# Connectors_1.net
KiCad netlist of a schematic drawn in Altium Designer
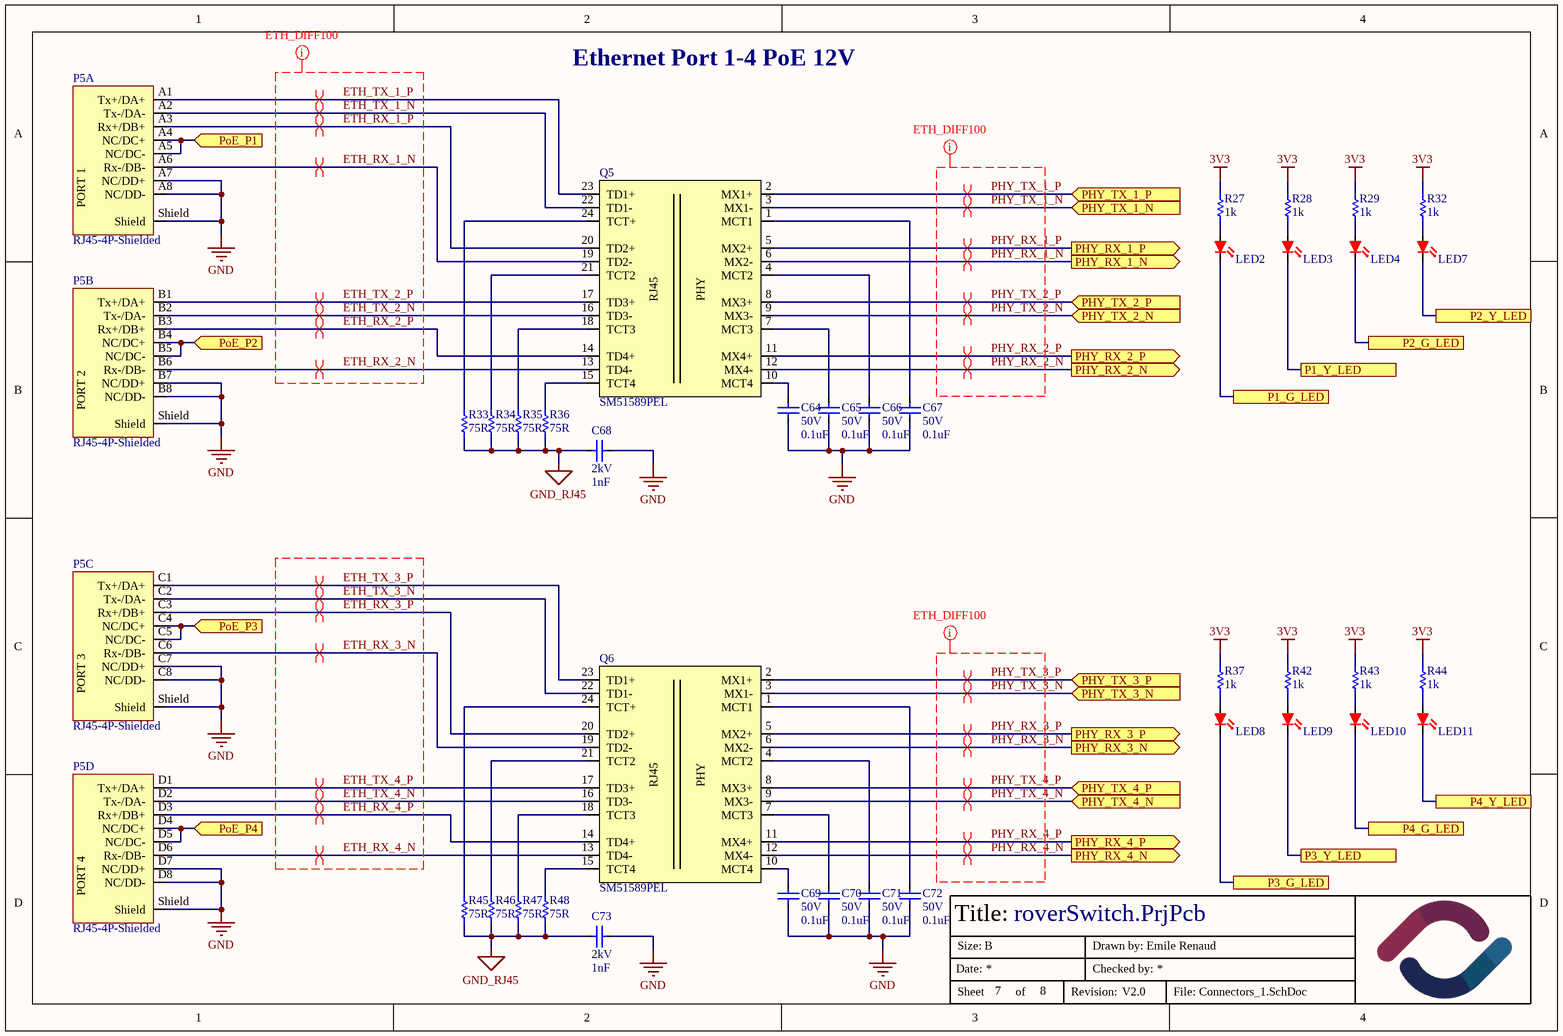
[diagram p0: Connectors_1.SchDoc]

(export (version "E")
  (design (tool "Eeschema 10.0.6"))
  (components
    (comp (ref "C64")
      (value "0.1uF")
      (footprint "CAPACITOR-0603")
      (description "Capacitor-0603-0.1uF-50V-X7R")
      (fields (field (name "VOLT") "50V"))
      (libsource (lib "Capacitors") (part "Capacitor-0603-0.1uF-50V-X7R"))
    )
    (comp (ref "C65")
      (value "0.1uF")
      (footprint "CAPACITOR-0603")
      (description "Capacitor-0603-0.1uF-50V-X7R")
      (fields (field (name "VOLT") "50V"))
      (libsource (lib "Capacitors") (part "Capacitor-0603-0.1uF-50V-X7R"))
    )
    (comp (ref "C66")
      (value "0.1uF")
      (footprint "CAPACITOR-0603")
      (description "Capacitor-0603-0.1uF-50V-X7R")
      (fields (field (name "VOLT") "50V"))
      (libsource (lib "Capacitors") (part "Capacitor-0603-0.1uF-50V-X7R"))
    )
    (comp (ref "C67")
      (value "0.1uF")
      (footprint "CAPACITOR-0603")
      (description "Capacitor-0603-0.1uF-50V-X7R")
      (fields (field (name "VOLT") "50V"))
      (libsource (lib "Capacitors") (part "Capacitor-0603-0.1uF-50V-X7R"))
    )
    (comp (ref "C68")
      (value "1nF")
      (footprint "CAPACITOR-1206")
      (description "Capacitor-1206-1nF-2kV-X7R")
      (fields (field (name "VOLT") "2kV"))
      (libsource (lib "Capacitors") (part "Capacitor-1206-1nF-2kV-X7R"))
    )
    (comp (ref "C69")
      (value "0.1uF")
      (footprint "CAPACITOR-0603")
      (description "Capacitor-0603-0.1uF-50V-X7R")
      (fields (field (name "VOLT") "50V"))
      (libsource (lib "Capacitors") (part "Capacitor-0603-0.1uF-50V-X7R"))
    )
    (comp (ref "C70")
      (value "0.1uF")
      (footprint "CAPACITOR-0603")
      (description "Capacitor-0603-0.1uF-50V-X7R")
      (fields (field (name "VOLT") "50V"))
      (libsource (lib "Capacitors") (part "Capacitor-0603-0.1uF-50V-X7R"))
    )
    (comp (ref "C71")
      (value "0.1uF")
      (footprint "CAPACITOR-0603")
      (description "Capacitor-0603-0.1uF-50V-X7R")
      (fields (field (name "VOLT") "50V"))
      (libsource (lib "Capacitors") (part "Capacitor-0603-0.1uF-50V-X7R"))
    )
    (comp (ref "C72")
      (value "0.1uF")
      (footprint "CAPACITOR-0603")
      (description "Capacitor-0603-0.1uF-50V-X7R")
      (fields (field (name "VOLT") "50V"))
      (libsource (lib "Capacitors") (part "Capacitor-0603-0.1uF-50V-X7R"))
    )
    (comp (ref "C73")
      (value "1nF")
      (footprint "CAPACITOR-1206")
      (description "Capacitor-1206-1nF-2kV-X7R")
      (fields (field (name "VOLT") "2kV"))
      (libsource (lib "Capacitors") (part "Capacitor-1206-1nF-2kV-X7R"))
    )
    (comp (ref "LED2")
      (value "B1911USD-20D000114U1930")
      (footprint "LED-0603-2PIN")
      (description "LED RED CLEAR 0603 SMD")
      (libsource (lib "LEDs") (part "B1911USD-20D000114U1930"))
    )
    (comp (ref "LED3")
      (value "B1911USD-20D000114U1930")
      (footprint "LED-0603-2PIN")
      (description "LED RED CLEAR 0603 SMD")
      (libsource (lib "LEDs") (part "B1911USD-20D000114U1930"))
    )
    (comp (ref "LED4")
      (value "B1911USD-20D000114U1930")
      (footprint "LED-0603-2PIN")
      (description "LED RED CLEAR 0603 SMD")
      (libsource (lib "LEDs") (part "B1911USD-20D000114U1930"))
    )
    (comp (ref "LED7")
      (value "B1911USD-20D000114U1930")
      (footprint "LED-0603-2PIN")
      (description "LED RED CLEAR 0603 SMD")
      (libsource (lib "LEDs") (part "B1911USD-20D000114U1930"))
    )
    (comp (ref "LED8")
      (value "B1911USD-20D000114U1930")
      (footprint "LED-0603-2PIN")
      (description "LED RED CLEAR 0603 SMD")
      (libsource (lib "LEDs") (part "B1911USD-20D000114U1930"))
    )
    (comp (ref "LED9")
      (value "B1911USD-20D000114U1930")
      (footprint "LED-0603-2PIN")
      (description "LED RED CLEAR 0603 SMD")
      (libsource (lib "LEDs") (part "B1911USD-20D000114U1930"))
    )
    (comp (ref "LED10")
      (value "B1911USD-20D000114U1930")
      (footprint "LED-0603-2PIN")
      (description "LED RED CLEAR 0603 SMD")
      (libsource (lib "LEDs") (part "B1911USD-20D000114U1930"))
    )
    (comp (ref "LED11")
      (value "B1911USD-20D000114U1930")
      (footprint "LED-0603-2PIN")
      (description "LED RED CLEAR 0603 SMD")
      (libsource (lib "LEDs") (part "B1911USD-20D000114U1930"))
    )
    (comp (ref "P5")
      (value "RJ45-4P-Shielded")
      (footprint "ETH_A00-432-262-450")
      (description "Jack Modular Connector 8p8c (RJ45, Ethernet) 90° Angle (Right) Shielded Cat5")
      (libsource (lib "PC-connector") (part "RJ45-4Ports"))
    )
    (comp (ref "Q5")
      (value "SM51589PEL")
      (footprint "SOIC24_BRN-M")
      (description "350µH LAN 10/100/1000 Base-T Pulse Transformer 1CT:1CT Surface Mount")
      (libsource (lib "Transformers-Magnetics") (part "SM51589PEL"))
    )
    (comp (ref "Q6")
      (value "SM51589PEL")
      (footprint "SOIC24_BRN-M")
      (description "350µH LAN 10/100/1000 Base-T Pulse Transformer 1CT:1CT Surface Mount")
      (libsource (lib "Transformers-Magnetics") (part "SM51589PEL"))
    )
    (comp (ref "R27")
      (value "1k")
      (footprint "Resistor-0603")
      (description "Resistor0603-1k")
      (fields (field (name "Comment") "SMT resistor"))
      (libsource (lib "Resistors") (part "Resistor-0603-1k"))
    )
    (comp (ref "R28")
      (value "1k")
      (footprint "Resistor-0603")
      (description "Resistor0603-1k")
      (fields (field (name "Comment") "SMT resistor"))
      (libsource (lib "Resistors") (part "Resistor-0603-1k"))
    )
    (comp (ref "R29")
      (value "1k")
      (footprint "Resistor-0603")
      (description "Resistor0603-1k")
      (fields (field (name "Comment") "SMT resistor"))
      (libsource (lib "Resistors") (part "Resistor-0603-1k"))
    )
    (comp (ref "R32")
      (value "1k")
      (footprint "Resistor-0603")
      (description "Resistor0603-1k")
      (fields (field (name "Comment") "SMT resistor"))
      (libsource (lib "Resistors") (part "Resistor-0603-1k"))
    )
    (comp (ref "R33")
      (value "75R")
      (footprint "Resistor-0603")
      (description "Resistor0603-75R")
      (fields (field (name "Comment") "SMT resistor"))
      (libsource (lib "Resistors") (part "Resistor-0603-75R"))
    )
    (comp (ref "R34")
      (value "75R")
      (footprint "Resistor-0603")
      (description "Resistor0603-75R")
      (fields (field (name "Comment") "SMT resistor"))
      (libsource (lib "Resistors") (part "Resistor-0603-75R"))
    )
    (comp (ref "R35")
      (value "75R")
      (footprint "Resistor-0603")
      (description "Resistor0603-75R")
      (fields (field (name "Comment") "SMT resistor"))
      (libsource (lib "Resistors") (part "Resistor-0603-75R"))
    )
    (comp (ref "R36")
      (value "75R")
      (footprint "Resistor-0603")
      (description "Resistor0603-75R")
      (fields (field (name "Comment") "SMT resistor"))
      (libsource (lib "Resistors") (part "Resistor-0603-75R"))
    )
    (comp (ref "R37")
      (value "1k")
      (footprint "Resistor-0603")
      (description "Resistor0603-1k")
      (fields (field (name "Comment") "SMT resistor"))
      (libsource (lib "Resistors") (part "Resistor-0603-1k"))
    )
    (comp (ref "R42")
      (value "1k")
      (footprint "Resistor-0603")
      (description "Resistor0603-1k")
      (fields (field (name "Comment") "SMT resistor"))
      (libsource (lib "Resistors") (part "Resistor-0603-1k"))
    )
    (comp (ref "R43")
      (value "1k")
      (footprint "Resistor-0603")
      (description "Resistor0603-1k")
      (fields (field (name "Comment") "SMT resistor"))
      (libsource (lib "Resistors") (part "Resistor-0603-1k"))
    )
    (comp (ref "R44")
      (value "1k")
      (footprint "Resistor-0603")
      (description "Resistor0603-1k")
      (fields (field (name "Comment") "SMT resistor"))
      (libsource (lib "Resistors") (part "Resistor-0603-1k"))
    )
    (comp (ref "R45")
      (value "75R")
      (footprint "Resistor-0603")
      (description "Resistor0603-75R")
      (fields (field (name "Comment") "SMT resistor"))
      (libsource (lib "Resistors") (part "Resistor-0603-75R"))
    )
    (comp (ref "R46")
      (value "75R")
      (footprint "Resistor-0603")
      (description "Resistor0603-75R")
      (fields (field (name "Comment") "SMT resistor"))
      (libsource (lib "Resistors") (part "Resistor-0603-75R"))
    )
    (comp (ref "R47")
      (value "75R")
      (footprint "Resistor-0603")
      (description "Resistor0603-75R")
      (fields (field (name "Comment") "SMT resistor"))
      (libsource (lib "Resistors") (part "Resistor-0603-75R"))
    )
    (comp (ref "R48")
      (value "75R")
      (footprint "Resistor-0603")
      (description "Resistor0603-75R")
      (fields (field (name "Comment") "SMT resistor"))
      (libsource (lib "Resistors") (part "Resistor-0603-75R"))
    )
  )
  (nets
    (net (code "1") (name "/ETH_RX_1_N") (class "Default")
      (node (ref "P5") (pin "A6") (pinfunction "Rx-/DB-_A6") (pintype "passive"))
      (node (ref "Q5") (pin "19") (pinfunction "TD2-_19") (pintype "passive"))
    )
    (net (code "2") (name "/ETH_RX_1_P") (class "Default")
      (node (ref "P5") (pin "A3") (pinfunction "Rx+/DB+_A3") (pintype "passive"))
      (node (ref "Q5") (pin "20") (pinfunction "TD2+_20") (pintype "passive"))
    )
    (net (code "3") (name "/ETH_RX_2_N") (class "Default")
      (node (ref "P5") (pin "B6") (pinfunction "Rx-/DB-_B6") (pintype "passive"))
      (node (ref "Q5") (pin "13") (pinfunction "TD4-_13") (pintype "passive"))
    )
    (net (code "4") (name "/ETH_RX_2_P") (class "Default")
      (node (ref "P5") (pin "B3") (pinfunction "Rx+/DB+_B3") (pintype "passive"))
      (node (ref "Q5") (pin "14") (pinfunction "TD4+_14") (pintype "passive"))
    )
    (net (code "5") (name "/ETH_RX_3_N") (class "Default")
      (node (ref "P5") (pin "C6") (pinfunction "Rx-/DB-_C6") (pintype "passive"))
      (node (ref "Q6") (pin "19") (pinfunction "TD2-_19") (pintype "passive"))
    )
    (net (code "6") (name "/ETH_RX_3_P") (class "Default")
      (node (ref "P5") (pin "C3") (pinfunction "Rx+/DB+_C3") (pintype "passive"))
      (node (ref "Q6") (pin "20") (pinfunction "TD2+_20") (pintype "passive"))
    )
    (net (code "7") (name "/ETH_RX_4_N") (class "Default")
      (node (ref "P5") (pin "D6") (pinfunction "Rx-/DB-_D6") (pintype "passive"))
      (node (ref "Q6") (pin "13") (pinfunction "TD4-_13") (pintype "passive"))
    )
    (net (code "8") (name "/ETH_RX_4_P") (class "Default")
      (node (ref "P5") (pin "D3") (pinfunction "Rx+/DB+_D3") (pintype "passive"))
      (node (ref "Q6") (pin "14") (pinfunction "TD4+_14") (pintype "passive"))
    )
    (net (code "9") (name "/ETH_TX_1_N") (class "Default")
      (node (ref "P5") (pin "A2") (pinfunction "Tx-/DA-_A2") (pintype "passive"))
      (node (ref "Q5") (pin "22") (pinfunction "TD1-_22") (pintype "passive"))
    )
    (net (code "10") (name "/ETH_TX_1_P") (class "Default")
      (node (ref "P5") (pin "A1") (pinfunction "Tx+/DA+_A1") (pintype "passive"))
      (node (ref "Q5") (pin "23") (pinfunction "TD1+_23") (pintype "passive"))
    )
    (net (code "11") (name "/ETH_TX_2_N") (class "Default")
      (node (ref "P5") (pin "B2") (pinfunction "Tx-/DA-_B2") (pintype "passive"))
      (node (ref "Q5") (pin "16") (pinfunction "TD3-_16") (pintype "passive"))
    )
    (net (code "12") (name "/ETH_TX_2_P") (class "Default")
      (node (ref "P5") (pin "B1") (pinfunction "Tx+/DA+_B1") (pintype "passive"))
      (node (ref "Q5") (pin "17") (pinfunction "TD3+_17") (pintype "passive"))
    )
    (net (code "13") (name "/ETH_TX_3_N") (class "Default")
      (node (ref "P5") (pin "C2") (pinfunction "Tx-/DA-_C2") (pintype "passive"))
      (node (ref "Q6") (pin "22") (pinfunction "TD1-_22") (pintype "passive"))
    )
    (net (code "14") (name "/ETH_TX_3_P") (class "Default")
      (node (ref "P5") (pin "C1") (pinfunction "Tx+/DA+_C1") (pintype "passive"))
      (node (ref "Q6") (pin "23") (pinfunction "TD1+_23") (pintype "passive"))
    )
    (net (code "15") (name "/ETH_TX_4_N") (class "Default")
      (node (ref "P5") (pin "D2") (pinfunction "Tx-/DA-_D2") (pintype "passive"))
      (node (ref "Q6") (pin "16") (pinfunction "TD3-_16") (pintype "passive"))
    )
    (net (code "16") (name "/ETH_TX_4_P") (class "Default")
      (node (ref "P5") (pin "D1") (pinfunction "Tx+/DA+_D1") (pintype "passive"))
      (node (ref "Q6") (pin "17") (pinfunction "TD3+_17") (pintype "passive"))
    )
    (net (code "17") (name "/P1_G_LED") (class "Default")
      (node (ref "LED2") (pin "1") (pinfunction "K_1") (pintype "passive"))
    )
    (net (code "18") (name "/P1_Y_LED") (class "Default")
      (node (ref "LED3") (pin "1") (pinfunction "K_1") (pintype "passive"))
    )
    (net (code "19") (name "/P2_G_LED") (class "Default")
      (node (ref "LED4") (pin "1") (pinfunction "K_1") (pintype "passive"))
    )
    (net (code "20") (name "/P2_Y_LED") (class "Default")
      (node (ref "LED7") (pin "1") (pinfunction "K_1") (pintype "passive"))
    )
    (net (code "21") (name "/P3_G_LED") (class "Default")
      (node (ref "LED8") (pin "1") (pinfunction "K_1") (pintype "passive"))
    )
    (net (code "22") (name "/P3_Y_LED") (class "Default")
      (node (ref "LED9") (pin "1") (pinfunction "K_1") (pintype "passive"))
    )
    (net (code "23") (name "/P4_G_LED") (class "Default")
      (node (ref "LED10") (pin "1") (pinfunction "K_1") (pintype "passive"))
    )
    (net (code "24") (name "/P4_Y_LED") (class "Default")
      (node (ref "LED11") (pin "1") (pinfunction "K_1") (pintype "passive"))
    )
    (net (code "25") (name "/PHY_RX_1_N") (class "Default")
      (node (ref "Q5") (pin "6") (pinfunction "MX2-_6") (pintype "passive"))
    )
    (net (code "26") (name "/PHY_RX_1_P") (class "Default")
      (node (ref "Q5") (pin "5") (pinfunction "MX2+_5") (pintype "passive"))
    )
    (net (code "27") (name "/PHY_RX_2_N") (class "Default")
      (node (ref "Q5") (pin "12") (pinfunction "MX4-_12") (pintype "passive"))
    )
    (net (code "28") (name "/PHY_RX_2_P") (class "Default")
      (node (ref "Q5") (pin "11") (pinfunction "MX4+_11") (pintype "passive"))
    )
    (net (code "29") (name "/PHY_RX_3_N") (class "Default")
      (node (ref "Q6") (pin "6") (pinfunction "MX2-_6") (pintype "passive"))
    )
    (net (code "30") (name "/PHY_RX_3_P") (class "Default")
      (node (ref "Q6") (pin "5") (pinfunction "MX2+_5") (pintype "passive"))
    )
    (net (code "31") (name "/PHY_RX_4_N") (class "Default")
      (node (ref "Q6") (pin "12") (pinfunction "MX4-_12") (pintype "passive"))
    )
    (net (code "32") (name "/PHY_RX_4_P") (class "Default")
      (node (ref "Q6") (pin "11") (pinfunction "MX4+_11") (pintype "passive"))
    )
    (net (code "33") (name "/PHY_TX_1_N") (class "Default")
      (node (ref "Q5") (pin "3") (pinfunction "MX1-_3") (pintype "passive"))
    )
    (net (code "34") (name "/PHY_TX_1_P") (class "Default")
      (node (ref "Q5") (pin "2") (pinfunction "MX1+_2") (pintype "passive"))
    )
    (net (code "35") (name "/PHY_TX_2_N") (class "Default")
      (node (ref "Q5") (pin "9") (pinfunction "MX3-_9") (pintype "passive"))
    )
    (net (code "36") (name "/PHY_TX_2_P") (class "Default")
      (node (ref "Q5") (pin "8") (pinfunction "MX3+_8") (pintype "passive"))
    )
    (net (code "37") (name "/PHY_TX_3_N") (class "Default")
      (node (ref "Q6") (pin "3") (pinfunction "MX1-_3") (pintype "passive"))
    )
    (net (code "38") (name "/PHY_TX_3_P") (class "Default")
      (node (ref "Q6") (pin "2") (pinfunction "MX1+_2") (pintype "passive"))
    )
    (net (code "39") (name "/PHY_TX_4_N") (class "Default")
      (node (ref "Q6") (pin "9") (pinfunction "MX3-_9") (pintype "passive"))
    )
    (net (code "40") (name "/PHY_TX_4_P") (class "Default")
      (node (ref "Q6") (pin "8") (pinfunction "MX3+_8") (pintype "passive"))
    )
    (net (code "41") (name "/PoE_P1") (class "Default")
      (node (ref "P5") (pin "A4") (pinfunction "NC/DC+_A4") (pintype "passive"))
      (node (ref "P5") (pin "A5") (pinfunction "NC/DC-_A5") (pintype "passive"))
    )
    (net (code "42") (name "/PoE_P2") (class "Default")
      (node (ref "P5") (pin "B4") (pinfunction "NC/DC+_B4") (pintype "passive"))
      (node (ref "P5") (pin "B5") (pinfunction "NC/DC-_B5") (pintype "passive"))
    )
    (net (code "43") (name "/PoE_P3") (class "Default")
      (node (ref "P5") (pin "C4") (pinfunction "NC/DC+_C4") (pintype "passive"))
      (node (ref "P5") (pin "C5") (pinfunction "NC/DC-_C5") (pintype "passive"))
    )
    (net (code "44") (name "/PoE_P4") (class "Default")
      (node (ref "P5") (pin "D4") (pinfunction "NC/DC+_D4") (pintype "passive"))
      (node (ref "P5") (pin "D5") (pinfunction "NC/DC-_D5") (pintype "passive"))
    )
    (net (code "45") (name "3V3") (class "Default")
      (node (ref "R27") (pin "2") (pinfunction "2_2") (pintype "passive"))
      (node (ref "R28") (pin "2") (pinfunction "2_2") (pintype "passive"))
      (node (ref "R29") (pin "2") (pinfunction "2_2") (pintype "passive"))
      (node (ref "R32") (pin "2") (pinfunction "2_2") (pintype "passive"))
      (node (ref "R37") (pin "2") (pinfunction "2_2") (pintype "passive"))
      (node (ref "R42") (pin "2") (pinfunction "2_2") (pintype "passive"))
      (node (ref "R43") (pin "2") (pinfunction "2_2") (pintype "passive"))
      (node (ref "R44") (pin "2") (pinfunction "2_2") (pintype "passive"))
    )
    (net (code "46") (name "GND") (class "Default")
      (node (ref "C64") (pin "1") (pinfunction "1_1") (pintype "passive"))
      (node (ref "C65") (pin "1") (pinfunction "1_1") (pintype "passive"))
      (node (ref "C66") (pin "1") (pinfunction "1_1") (pintype "passive"))
      (node (ref "C67") (pin "1") (pinfunction "1_1") (pintype "passive"))
      (node (ref "C68") (pin "2") (pinfunction "2_2") (pintype "passive"))
      (node (ref "C69") (pin "1") (pinfunction "1_1") (pintype "passive"))
      (node (ref "C70") (pin "1") (pinfunction "1_1") (pintype "passive"))
      (node (ref "C71") (pin "1") (pinfunction "1_1") (pintype "passive"))
      (node (ref "C72") (pin "1") (pinfunction "1_1") (pintype "passive"))
      (node (ref "C73") (pin "2") (pinfunction "2_2") (pintype "passive"))
      (node (ref "P5") (pin "A7") (pinfunction "NC/DD+_A7") (pintype "passive"))
      (node (ref "P5") (pin "A8") (pinfunction "NC/DD-_A8") (pintype "passive"))
      (node (ref "P5") (pin "B7") (pinfunction "NC/DD+_B7") (pintype "passive"))
      (node (ref "P5") (pin "B8") (pinfunction "NC/DD-_B8") (pintype "passive"))
      (node (ref "P5") (pin "C7") (pinfunction "NC/DD+_C7") (pintype "passive"))
      (node (ref "P5") (pin "C8") (pinfunction "NC/DD-_C8") (pintype "passive"))
      (node (ref "P5") (pin "D7") (pinfunction "NC/DD+_D7") (pintype "passive"))
      (node (ref "P5") (pin "D8") (pinfunction "NC/DD-_D8") (pintype "passive"))
      (node (ref "P5") (pin "Shield") (pinfunction "Shield_Shield") (pintype "passive"))
    )
    (net (code "47") (name "GND_RJ45") (class "Default")
      (node (ref "C68") (pin "1") (pinfunction "1_1") (pintype "passive"))
      (node (ref "C73") (pin "1") (pinfunction "1_1") (pintype "passive"))
      (node (ref "R33") (pin "1") (pinfunction "1_1") (pintype "passive"))
      (node (ref "R34") (pin "1") (pinfunction "1_1") (pintype "passive"))
      (node (ref "R35") (pin "1") (pinfunction "1_1") (pintype "passive"))
      (node (ref "R36") (pin "1") (pinfunction "1_1") (pintype "passive"))
      (node (ref "R45") (pin "1") (pinfunction "1_1") (pintype "passive"))
      (node (ref "R46") (pin "1") (pinfunction "1_1") (pintype "passive"))
      (node (ref "R47") (pin "1") (pinfunction "1_1") (pintype "passive"))
      (node (ref "R48") (pin "1") (pinfunction "1_1") (pintype "passive"))
    )
    (net (code "48") (name "Net-(LED2-R)") (class "Default")
      (node (ref "LED2") (pin "2") (pinfunction "R_2") (pintype "passive"))
      (node (ref "R27") (pin "1") (pinfunction "1_1") (pintype "passive"))
    )
    (net (code "49") (name "Net-(LED3-R)") (class "Default")
      (node (ref "LED3") (pin "2") (pinfunction "R_2") (pintype "passive"))
      (node (ref "R28") (pin "1") (pinfunction "1_1") (pintype "passive"))
    )
    (net (code "50") (name "Net-(LED4-R)") (class "Default")
      (node (ref "LED4") (pin "2") (pinfunction "R_2") (pintype "passive"))
      (node (ref "R29") (pin "1") (pinfunction "1_1") (pintype "passive"))
    )
    (net (code "51") (name "Net-(LED7-R)") (class "Default")
      (node (ref "LED7") (pin "2") (pinfunction "R_2") (pintype "passive"))
      (node (ref "R32") (pin "1") (pinfunction "1_1") (pintype "passive"))
    )
    (net (code "52") (name "Net-(LED8-R)") (class "Default")
      (node (ref "LED8") (pin "2") (pinfunction "R_2") (pintype "passive"))
      (node (ref "R37") (pin "1") (pinfunction "1_1") (pintype "passive"))
    )
    (net (code "53") (name "Net-(LED9-R)") (class "Default")
      (node (ref "LED9") (pin "2") (pinfunction "R_2") (pintype "passive"))
      (node (ref "R42") (pin "1") (pinfunction "1_1") (pintype "passive"))
    )
    (net (code "54") (name "Net-(LED10-R)") (class "Default")
      (node (ref "LED10") (pin "2") (pinfunction "R_2") (pintype "passive"))
      (node (ref "R43") (pin "1") (pinfunction "1_1") (pintype "passive"))
    )
    (net (code "55") (name "Net-(LED11-R)") (class "Default")
      (node (ref "LED11") (pin "2") (pinfunction "R_2") (pintype "passive"))
      (node (ref "R44") (pin "1") (pinfunction "1_1") (pintype "passive"))
    )
    (net (code "56") (name "Net-(Q5-MCT1)") (class "Default")
      (node (ref "C67") (pin "2") (pinfunction "2_2") (pintype "passive"))
      (node (ref "Q5") (pin "1") (pinfunction "MCT1_1") (pintype "passive"))
    )
    (net (code "57") (name "Net-(Q5-MCT2)") (class "Default")
      (node (ref "C66") (pin "2") (pinfunction "2_2") (pintype "passive"))
      (node (ref "Q5") (pin "4") (pinfunction "MCT2_4") (pintype "passive"))
    )
    (net (code "58") (name "Net-(Q5-MCT3)") (class "Default")
      (node (ref "C65") (pin "2") (pinfunction "2_2") (pintype "passive"))
      (node (ref "Q5") (pin "7") (pinfunction "MCT3_7") (pintype "passive"))
    )
    (net (code "59") (name "Net-(Q5-MCT4)") (class "Default")
      (node (ref "C64") (pin "2") (pinfunction "2_2") (pintype "passive"))
      (node (ref "Q5") (pin "10") (pinfunction "MCT4_10") (pintype "passive"))
    )
    (net (code "60") (name "Net-(Q5-TCT+)") (class "Default")
      (node (ref "Q5") (pin "24") (pinfunction "TCT+_24") (pintype "passive"))
      (node (ref "R33") (pin "2") (pinfunction "2_2") (pintype "passive"))
    )
    (net (code "61") (name "Net-(Q5-TCT2)") (class "Default")
      (node (ref "Q5") (pin "21") (pinfunction "TCT2_21") (pintype "passive"))
      (node (ref "R34") (pin "2") (pinfunction "2_2") (pintype "passive"))
    )
    (net (code "62") (name "Net-(Q5-TCT3)") (class "Default")
      (node (ref "Q5") (pin "18") (pinfunction "TCT3_18") (pintype "passive"))
      (node (ref "R35") (pin "2") (pinfunction "2_2") (pintype "passive"))
    )
    (net (code "63") (name "Net-(Q5-TCT4)") (class "Default")
      (node (ref "Q5") (pin "15") (pinfunction "TCT4_15") (pintype "passive"))
      (node (ref "R36") (pin "2") (pinfunction "2_2") (pintype "passive"))
    )
    (net (code "64") (name "Net-(Q6-MCT1)") (class "Default")
      (node (ref "C72") (pin "2") (pinfunction "2_2") (pintype "passive"))
      (node (ref "Q6") (pin "1") (pinfunction "MCT1_1") (pintype "passive"))
    )
    (net (code "65") (name "Net-(Q6-MCT2)") (class "Default")
      (node (ref "C71") (pin "2") (pinfunction "2_2") (pintype "passive"))
      (node (ref "Q6") (pin "4") (pinfunction "MCT2_4") (pintype "passive"))
    )
    (net (code "66") (name "Net-(Q6-MCT3)") (class "Default")
      (node (ref "C70") (pin "2") (pinfunction "2_2") (pintype "passive"))
      (node (ref "Q6") (pin "7") (pinfunction "MCT3_7") (pintype "passive"))
    )
    (net (code "67") (name "Net-(Q6-MCT4)") (class "Default")
      (node (ref "C69") (pin "2") (pinfunction "2_2") (pintype "passive"))
      (node (ref "Q6") (pin "10") (pinfunction "MCT4_10") (pintype "passive"))
    )
    (net (code "68") (name "Net-(Q6-TCT+)") (class "Default")
      (node (ref "Q6") (pin "24") (pinfunction "TCT+_24") (pintype "passive"))
      (node (ref "R45") (pin "2") (pinfunction "2_2") (pintype "passive"))
    )
    (net (code "69") (name "Net-(Q6-TCT2)") (class "Default")
      (node (ref "Q6") (pin "21") (pinfunction "TCT2_21") (pintype "passive"))
      (node (ref "R46") (pin "2") (pinfunction "2_2") (pintype "passive"))
    )
    (net (code "70") (name "Net-(Q6-TCT3)") (class "Default")
      (node (ref "Q6") (pin "18") (pinfunction "TCT3_18") (pintype "passive"))
      (node (ref "R47") (pin "2") (pinfunction "2_2") (pintype "passive"))
    )
    (net (code "71") (name "Net-(Q6-TCT4)") (class "Default")
      (node (ref "Q6") (pin "15") (pinfunction "TCT4_15") (pintype "passive"))
      (node (ref "R48") (pin "2") (pinfunction "2_2") (pintype "passive"))
    )
  )
)
